# PIN_3_Sch.net
KiCad netlist of a schematic drawn in Altium Designer
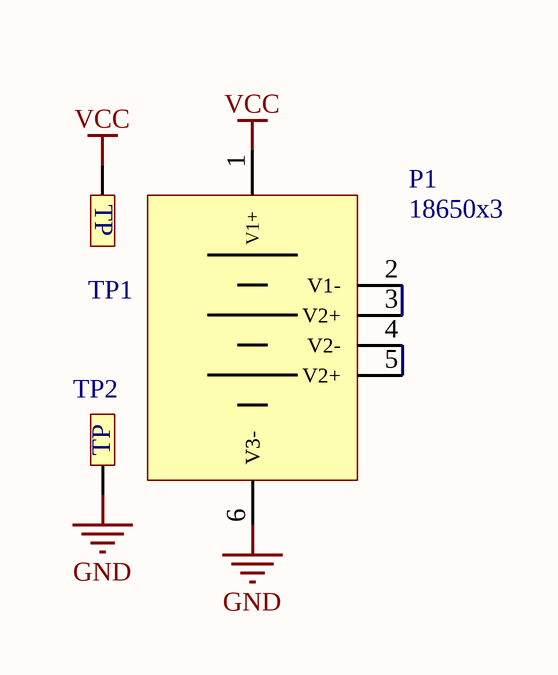
[diagram p0: PIN_3_Sch.SchDoc]

(export (version "E")
  (design (tool "Eeschema 10.0.6"))
  (components
    (comp (ref "P1") (value "18650x3") (footprint "18650x3") (libsource (lib "Hold_18650x3") (part "Power")))
    (comp (ref "TP1") (value "Test Point") (footprint "TP") (libsource (lib "") (part "Test Point_1")))
    (comp (ref "TP2")
      (value "Test Point")
      (footprint "TP")
      (libsource (lib "PIF_Library") (part "Test Point"))
    )
  )
  (nets
    (net (code "1") (name "GND") (class "Default")
      (node (ref "P1") (pin "6") (pinfunction "V3-_6") (pintype "passive"))
      (node (ref "TP2") (pin "TP1") (pinfunction "0_TP1") (pintype "passive"))
    )
    (net (code "2") (name "Net-(P1-V1-)") (class "Default")
      (node (ref "P1") (pin "2") (pinfunction "V1-_2") (pintype "passive"))
      (node (ref "P1") (pin "3") (pinfunction "V2+_3") (pintype "passive"))
    )
    (net (code "3") (name "Net-(P1-V2-)") (class "Default")
      (node (ref "P1") (pin "4") (pinfunction "V2-_4") (pintype "passive"))
      (node (ref "P1") (pin "5") (pinfunction "V2+_5") (pintype "passive"))
    )
    (net (code "4") (name "VCC") (class "Default")
      (node (ref "P1") (pin "1") (pinfunction "V1+_1") (pintype "passive"))
      (node (ref "TP1") (pin "TP1") (pinfunction "0_TP1") (pintype "passive"))
    )
  )
)
